# 70_MODULE_INTERFACE.net
KiCad netlist of a schematic drawn in Altium Designer
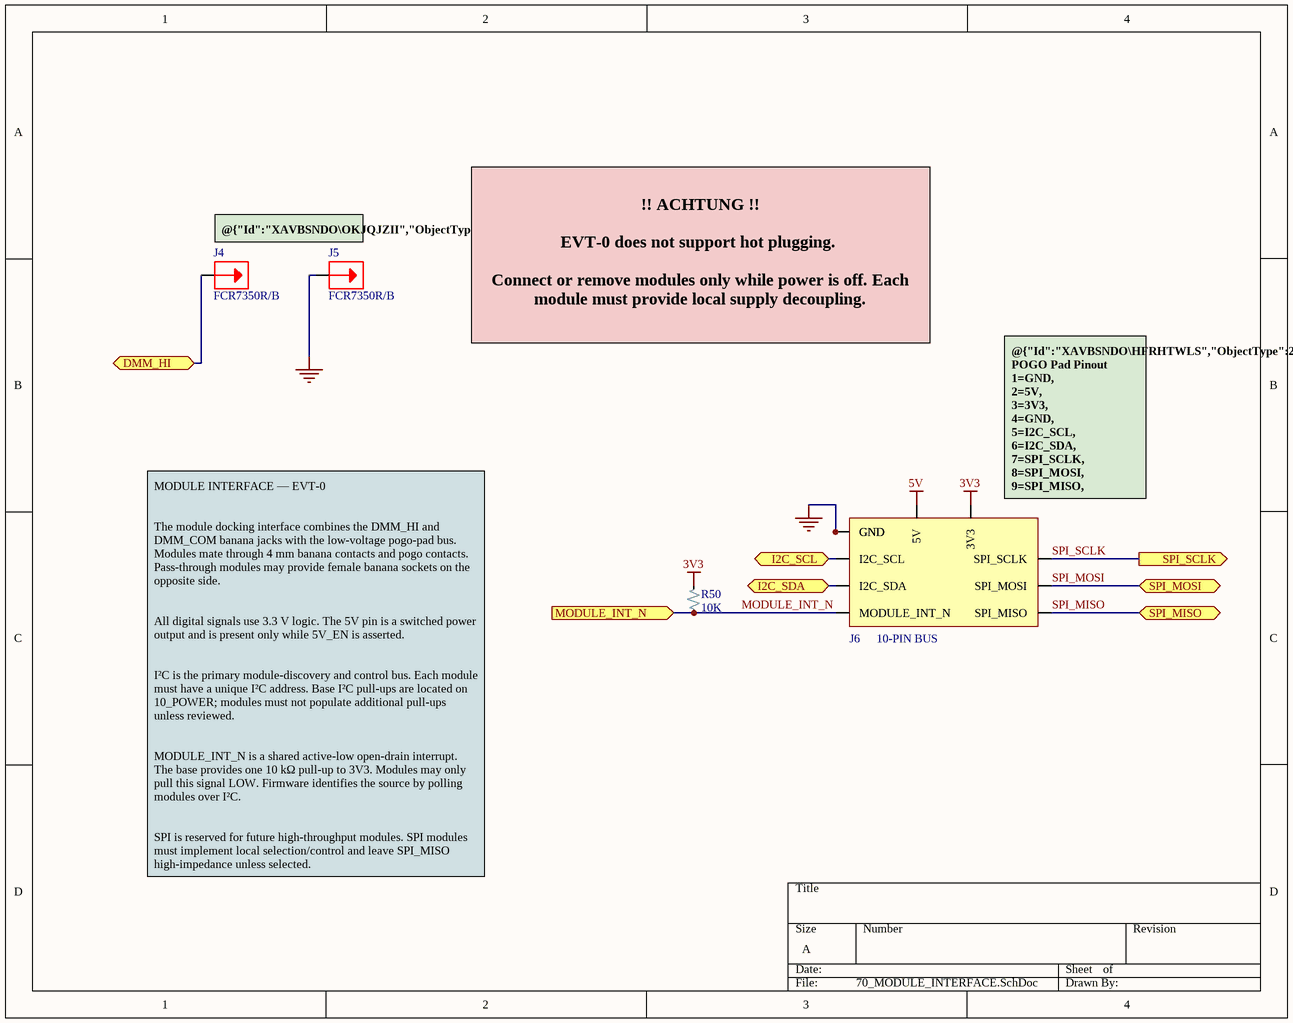
[diagram p0: 70_MODULE_INTERFACE.SchDoc]

(export (version "E")
  (design (tool "Eeschema 10.0.6"))
  (components
    (comp (ref "J4")
      (value "FCR7350R/B")
      (footprint "FCR7350_S16-PC")
      (description "4 mm shrouded banana socket, PCB mount")
      (fields (field (name "MANUFACTURER") "Cliff") (field (name "MANUFACTURER PART NUMBER") "FCR7350R"))
      (libsource (lib "PocketLab_DMM_EVT0") (part "FCR7350"))
    )
    (comp (ref "J5")
      (value "FCR7350R/B")
      (footprint "FCR7350_S16-PC")
      (description "4 mm shrouded banana socket, PCB mount")
      (fields (field (name "MANUFACTURER") "Cliff") (field (name "MANUFACTURER PART NUMBER") "FCR7350R"))
      (libsource (lib "PocketLab_DMM_EVT0") (part "FCR7350"))
    )
    (comp (ref "J6")
      (value "10-PIN BUS")
      (footprint "MODULE_BUS_10_TAB_SLOT")
      (description "10-pin stackable module interface for power, I2C, SPI, and shared interrupt")
      (libsource (lib "PocketLab_DMM_SchLib") (part "J_MODULE_BUS"))
    )
    (comp (ref "R50")
      (value "10K")
      (footprint "R0805")
      (description "RES 1/8W 0805")
      (fields
        (field (name "MANUFACTURER") "Stackpole Electronics")
        (field (name "MANUFACTURER PART NUMBER") "RNCF0805TKY10K0")
      )
      (libsource (lib "PocketLab_DMM_SchLib") (part "R_0805"))
    )
  )
  (nets
    (net (code "1") (name "/DMM_HI") (class "Default")
      (node (ref "J4") (pin "1") (pinfunction "IN_1") (pintype "passive"))
    )
    (net (code "2") (name "/I2C_SCL") (class "Default")
      (node (ref "J6") (pin "5") (pinfunction "I2C_SCL_5") (pintype "passive"))
    )
    (net (code "3") (name "/I2C_SDA") (class "Default")
      (node (ref "J6") (pin "6") (pinfunction "I2C_SDA_6") (pintype "passive"))
    )
    (net (code "4") (name "/MODULE_INT_N") (class "Default")
      (node (ref "J6") (pin "10") (pinfunction "MODULE_INT_N_10") (pintype "passive"))
      (node (ref "R50") (pin "1") (pinfunction "1_1") (pintype "passive"))
    )
    (net (code "5") (name "/SPI_MISO") (class "Default")
      (node (ref "J6") (pin "9") (pinfunction "SPI_MISO_9") (pintype "passive"))
    )
    (net (code "6") (name "/SPI_MOSI") (class "Default")
      (node (ref "J6") (pin "8") (pinfunction "SPI_MOSI_8") (pintype "passive"))
    )
    (net (code "7") (name "/SPI_SCLK") (class "Default")
      (node (ref "J6") (pin "7") (pinfunction "SPI_SCLK_7") (pintype "passive"))
    )
    (net (code "8") (name "3V3") (class "Default")
      (node (ref "J6") (pin "3") (pinfunction "3V3_3") (pintype "passive"))
      (node (ref "R50") (pin "2") (pinfunction "2_2") (pintype "passive"))
    )
    (net (code "9") (name "5V") (class "Default")
      (node (ref "J6") (pin "2") (pinfunction "5V_2") (pintype "passive"))
    )
    (net (code "10") (name "GND") (class "Default")
      (node (ref "J5") (pin "1") (pinfunction "IN_1") (pintype "passive"))
      (node (ref "J6") (pin "1") (pinfunction "GND_1") (pintype "passive"))
      (node (ref "J6") (pin "4") (pinfunction "GND_4") (pintype "passive"))
    )
  )
)
